# ProPrj_STC-FOC__2026-02-01.net
KiCad netlist of a schematic drawn in EasyEDA Pro
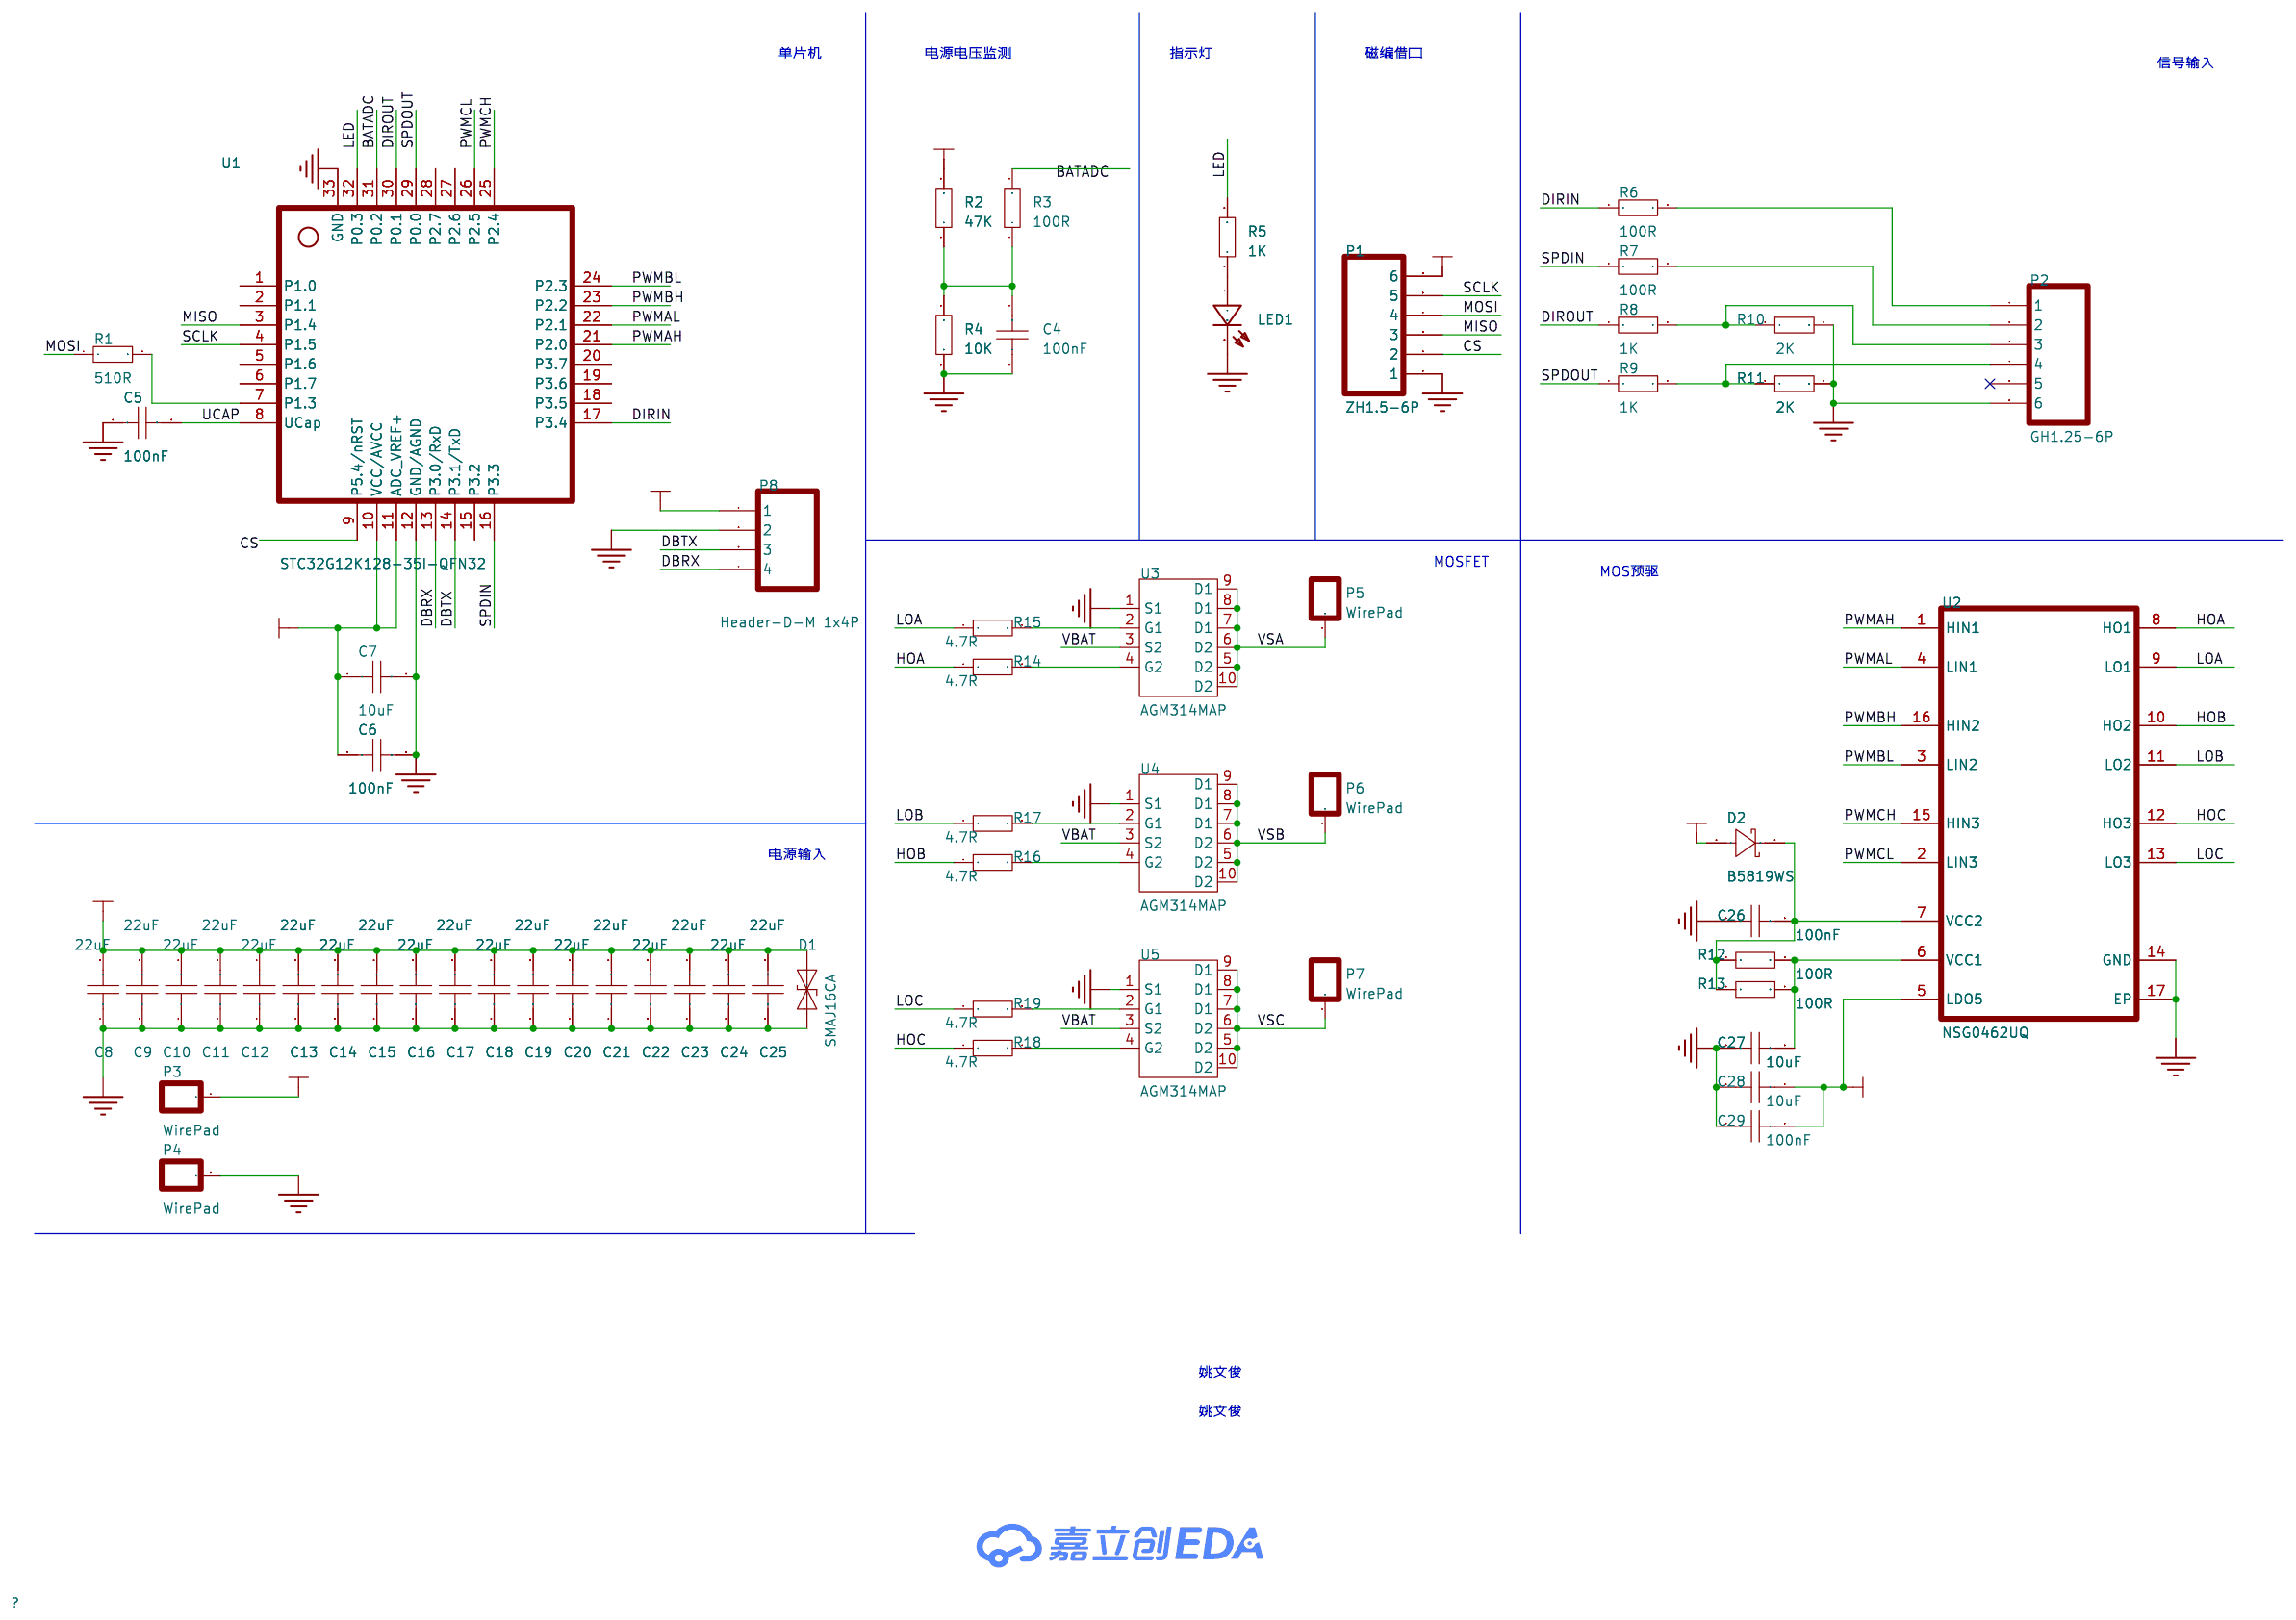
[diagram p0: schematic sheet]

(export (version "E")
  (design (tool "Eeschema 10.0.6"))
  (components
    (comp (ref "C4")
      (value "100nF")
      (footprint "easyedapro:C0603")
      (libsource (lib "easyedapro") (part "Capacitance"))
    )
    (comp (ref "C5")
      (value "100nF")
      (footprint "easyedapro:C0603")
      (libsource (lib "easyedapro") (part "Capacitance"))
    )
    (comp (ref "C6")
      (value "100nF")
      (footprint "easyedapro:C0603")
      (libsource (lib "easyedapro") (part "Capacitance"))
    )
    (comp (ref "C7")
      (value "10uF")
      (footprint "easyedapro:C0603")
      (libsource (lib "easyedapro") (part "Capacitance"))
    )
    (comp (ref "C8")
      (value "22uF")
      (footprint "easyedapro:C0603")
      (libsource (lib "easyedapro") (part "Capacitance"))
    )
    (comp (ref "C9")
      (value "22uF")
      (footprint "easyedapro:C0603")
      (libsource (lib "easyedapro") (part "Capacitance"))
    )
    (comp (ref "C10")
      (value "22uF")
      (footprint "easyedapro:C0603")
      (libsource (lib "easyedapro") (part "Capacitance"))
    )
    (comp (ref "C11")
      (value "22uF")
      (footprint "easyedapro:C0603")
      (libsource (lib "easyedapro") (part "Capacitance"))
    )
    (comp (ref "C12")
      (value "22uF")
      (footprint "easyedapro:C0603")
      (libsource (lib "easyedapro") (part "Capacitance"))
    )
    (comp (ref "C13")
      (value "22uF")
      (footprint "easyedapro:C0603")
      (libsource (lib "easyedapro") (part "Capacitance"))
    )
    (comp (ref "C14")
      (value "22uF")
      (footprint "easyedapro:C0603")
      (libsource (lib "easyedapro") (part "Capacitance"))
    )
    (comp (ref "C15")
      (value "22uF")
      (footprint "easyedapro:C0603")
      (libsource (lib "easyedapro") (part "Capacitance"))
    )
    (comp (ref "C16")
      (value "22uF")
      (footprint "easyedapro:C0603")
      (libsource (lib "easyedapro") (part "Capacitance"))
    )
    (comp (ref "C17")
      (value "22uF")
      (footprint "easyedapro:C0603")
      (libsource (lib "easyedapro") (part "Capacitance"))
    )
    (comp (ref "C18")
      (value "22uF")
      (footprint "easyedapro:C0603")
      (libsource (lib "easyedapro") (part "Capacitance"))
    )
    (comp (ref "C19")
      (value "22uF")
      (footprint "easyedapro:C0603")
      (libsource (lib "easyedapro") (part "Capacitance"))
    )
    (comp (ref "C20")
      (value "22uF")
      (footprint "easyedapro:C0603")
      (libsource (lib "easyedapro") (part "Capacitance"))
    )
    (comp (ref "C21")
      (value "22uF")
      (footprint "easyedapro:C0603")
      (libsource (lib "easyedapro") (part "Capacitance"))
    )
    (comp (ref "C22")
      (value "22uF")
      (footprint "easyedapro:C0603")
      (libsource (lib "easyedapro") (part "Capacitance"))
    )
    (comp (ref "C23")
      (value "22uF")
      (footprint "easyedapro:C0603")
      (libsource (lib "easyedapro") (part "Capacitance"))
    )
    (comp (ref "C24")
      (value "22uF")
      (footprint "easyedapro:C0603")
      (libsource (lib "easyedapro") (part "Capacitance"))
    )
    (comp (ref "C25")
      (value "22uF")
      (footprint "easyedapro:C0603")
      (libsource (lib "easyedapro") (part "Capacitance"))
    )
    (comp (ref "C26")
      (value "100nF")
      (footprint "easyedapro:C0603")
      (libsource (lib "easyedapro") (part "Capacitance"))
    )
    (comp (ref "C27")
      (value "10uF")
      (footprint "easyedapro:C0603")
      (libsource (lib "easyedapro") (part "Capacitance"))
    )
    (comp (ref "C28")
      (value "10uF")
      (footprint "easyedapro:C0603")
      (libsource (lib "easyedapro") (part "Capacitance"))
    )
    (comp (ref "C29")
      (value "100nF")
      (footprint "easyedapro:C0603")
      (libsource (lib "easyedapro") (part "Capacitance"))
    )
    (comp (ref "D1")
      (value "SMAJ16CA")
      (footprint "easyedapro:SMA_L4.4-W2.6-LS5.0-BI")
      (description "极性:双向;反向截止电压(Vrwm):16V;钳位电压:26V;峰值脉冲电流(Ipp):15.38A;峰值脉冲功率(Ppp):400W@10/1000us;击穿电压:17.8V;")
      (fields (field (name "Manufacturer") "DOWO(东沃)"))
      (libsource (lib "easyedapro") (part "SMAJ16CA_C356365"))
    )
    (comp (ref "D2")
      (value "B5819WS")
      (footprint "easyedapro:SOD-323_L1.7-W1.3-LS2.7-RD")
      (description "二极管配置:1个独立式;正向压降(Vf):900mV@3A;直流反向耐压(Vr):40V;整流电流:1A;")
      (fields (field (name "Manufacturer") "CCX(晁禾)"))
      (libsource (lib "easyedapro") (part "B5819WS_C51953485"))
    )
    (comp (ref "LED1")
      (value "LED Chip Blue")
      (footprint "easyedapro:LEDC1608(0603)-L")
      (description "蓝色贴片LED")
      (libsource (lib "easyedapro") (part "LED Chip Blue"))
    )
    (comp (ref "P1")
      (value "ZH1.5-6P")
      (footprint "easyedapro:ZH1.5-6P-SH")
      (libsource (lib "easyedapro") (part "ZH1.5-6P"))
    )
    (comp (ref "P2")
      (value "GH1.25-6P")
      (footprint "easyedapro:GH1.25-6P-SH")
      (libsource (lib "easyedapro") (part "GH1.25-6P"))
    )
    (comp (ref "P3")
      (value "WirePad")
      (footprint "easyedapro:WirePad-3x4")
      (description "线缆焊盘")
      (libsource (lib "easyedapro") (part "WirePad"))
    )
    (comp (ref "P4")
      (value "WirePad")
      (footprint "easyedapro:WirePad-3x4")
      (description "线缆焊盘")
      (libsource (lib "easyedapro") (part "WirePad"))
    )
    (comp (ref "P5")
      (value "WirePad")
      (footprint "easyedapro:WirePad-3x4")
      (description "线缆焊盘")
      (libsource (lib "easyedapro") (part "WirePad"))
    )
    (comp (ref "P6")
      (value "WirePad")
      (footprint "easyedapro:WirePad-3x4")
      (description "线缆焊盘")
      (libsource (lib "easyedapro") (part "WirePad"))
    )
    (comp (ref "P7")
      (value "WirePad")
      (footprint "easyedapro:WirePad-3x4")
      (description "线缆焊盘")
      (libsource (lib "easyedapro") (part "WirePad"))
    )
    (comp (ref "P8")
      (value "Header-D-M 1x4P")
      (footprint "easyedapro:HDR1X4-M")
      (description "1x4pin, 直插, 排针")
      (libsource (lib "easyedapro") (part "Header-D-M 1x4P"))
    )
    (comp (ref "R1") (value "510R") (footprint "easyedapro:R0402") (libsource (lib "easyedapro") (part "电阻")))
    (comp (ref "R2") (value "47K") (footprint "easyedapro:R0402") (libsource (lib "easyedapro") (part "电阻")))
    (comp (ref "R3") (value "100R") (footprint "easyedapro:R0402") (libsource (lib "easyedapro") (part "电阻")))
    (comp (ref "R4") (value "10K") (footprint "easyedapro:R0402") (libsource (lib "easyedapro") (part "电阻")))
    (comp (ref "R5") (value "1K") (footprint "easyedapro:R0402") (libsource (lib "easyedapro") (part "电阻")))
    (comp (ref "R6") (value "100R") (footprint "easyedapro:R0402") (libsource (lib "easyedapro") (part "电阻")))
    (comp (ref "R7") (value "100R") (footprint "easyedapro:R0402") (libsource (lib "easyedapro") (part "电阻")))
    (comp (ref "R8") (value "1K") (footprint "easyedapro:R0402") (libsource (lib "easyedapro") (part "电阻")))
    (comp (ref "R9") (value "1K") (footprint "easyedapro:R0402") (libsource (lib "easyedapro") (part "电阻")))
    (comp (ref "R10") (value "2K") (footprint "easyedapro:R0402") (libsource (lib "easyedapro") (part "电阻")))
    (comp (ref "R11") (value "2K") (footprint "easyedapro:R0402") (libsource (lib "easyedapro") (part "电阻")))
    (comp (ref "R12")
      (value "100R")
      (footprint "easyedapro:R0402")
      (libsource (lib "easyedapro") (part "电阻"))
    )
    (comp (ref "R13")
      (value "100R")
      (footprint "easyedapro:R0402")
      (libsource (lib "easyedapro") (part "电阻"))
    )
    (comp (ref "R14")
      (value "4.7R")
      (footprint "easyedapro:R0402")
      (libsource (lib "easyedapro") (part "电阻"))
    )
    (comp (ref "R15")
      (value "4.7R")
      (footprint "easyedapro:R0402")
      (libsource (lib "easyedapro") (part "电阻"))
    )
    (comp (ref "R16")
      (value "4.7R")
      (footprint "easyedapro:R0402")
      (libsource (lib "easyedapro") (part "电阻"))
    )
    (comp (ref "R17")
      (value "4.7R")
      (footprint "easyedapro:R0402")
      (libsource (lib "easyedapro") (part "电阻"))
    )
    (comp (ref "R18")
      (value "4.7R")
      (footprint "easyedapro:R0402")
      (libsource (lib "easyedapro") (part "电阻"))
    )
    (comp (ref "R19")
      (value "4.7R")
      (footprint "easyedapro:R0402")
      (libsource (lib "easyedapro") (part "电阻"))
    )
    (comp (ref "U1")
      (value "STC32G12K128-35I-QFN32")
      (footprint "easyedapro:QFN32-4x4")
      (libsource (lib "easyedapro") (part "STC32G12K128-35I-QFN32"))
    )
    (comp (ref "U2")
      (value "NSG0462UQ")
      (footprint "easyedapro:QFN16-3x3-0.5")
      (description "NSG0462UQ 三相栅极驱动器")
      (libsource (lib "easyedapro") (part "NSG0462UQ"))
    )
    (comp (ref "U3")
      (value "AGM314MAP")
      (footprint "easyedapro:PDFN-8_L3.2-W3.1-P0.65-LS3.4-BL-EP2")
      (fields (field (name "Manufacturer") "AGMSEMI(芯控源)"))
      (libsource (lib "easyedapro") (part "AGM314MAP"))
    )
    (comp (ref "U4")
      (value "AGM314MAP")
      (footprint "easyedapro:PDFN-8_L3.2-W3.1-P0.65-LS3.4-BL-EP2")
      (fields (field (name "Manufacturer") "AGMSEMI(芯控源)"))
      (libsource (lib "easyedapro") (part "AGM314MAP"))
    )
    (comp (ref "U5")
      (value "AGM314MAP")
      (footprint "easyedapro:PDFN-8_L3.2-W3.1-P0.65-LS3.4-BL-EP2")
      (fields (field (name "Manufacturer") "AGMSEMI(芯控源)"))
      (libsource (lib "easyedapro") (part "AGM314MAP"))
    )
  )
  (nets
    (net (code "1") (name "/BATADC") (class "Default")
      (node (ref "R3") (pin "2") (pinfunction "2_2") (pintype "input"))
      (node (ref "U1") (pin "31") (pinfunction "P0.2_31") (pintype "unspecified"))
    )
    (net (code "2") (name "/CS") (class "Default")
      (node (ref "P1") (pin "2") (pinfunction "2_2") (pintype "unspecified"))
      (node (ref "U1") (pin "9") (pinfunction "P5.4/nRST_9") (pintype "unspecified"))
    )
    (net (code "3") (name "/DBRX") (class "Default")
      (node (ref "P8") (pin "4") (pinfunction "4_4") (pintype "unspecified"))
      (node (ref "U1") (pin "13") (pinfunction "P3.0/RxD_13") (pintype "unspecified"))
    )
    (net (code "4") (name "/DBTX") (class "Default")
      (node (ref "P8") (pin "3") (pinfunction "3_3") (pintype "unspecified"))
      (node (ref "U1") (pin "14") (pinfunction "P3.1/TxD_14") (pintype "unspecified"))
    )
    (net (code "5") (name "/DIRIN") (class "Default")
      (node (ref "R6") (pin "1") (pinfunction "1_1") (pintype "input"))
      (node (ref "U1") (pin "17") (pinfunction "P3.4_17") (pintype "unspecified"))
    )
    (net (code "6") (name "/DIROUT") (class "Default")
      (node (ref "R8") (pin "1") (pinfunction "1_1") (pintype "input"))
      (node (ref "U1") (pin "30") (pinfunction "P0.1_30") (pintype "unspecified"))
    )
    (net (code "7") (name "/HOA") (class "Default")
      (node (ref "R14") (pin "1") (pinfunction "1_1") (pintype "input"))
      (node (ref "U2") (pin "8") (pinfunction "HO1_8") (pintype "unspecified"))
    )
    (net (code "8") (name "/HOB") (class "Default")
      (node (ref "R16") (pin "1") (pinfunction "1_1") (pintype "input"))
      (node (ref "U2") (pin "10") (pinfunction "HO2_10") (pintype "unspecified"))
    )
    (net (code "9") (name "/HOC") (class "Default")
      (node (ref "R18") (pin "1") (pinfunction "1_1") (pintype "input"))
      (node (ref "U2") (pin "12") (pinfunction "HO3_12") (pintype "unspecified"))
    )
    (net (code "10") (name "/LED") (class "Default")
      (node (ref "R5") (pin "2") (pinfunction "2_2") (pintype "input"))
      (node (ref "U1") (pin "32") (pinfunction "P0.3_32") (pintype "unspecified"))
    )
    (net (code "11") (name "/LOA") (class "Default")
      (node (ref "R15") (pin "1") (pinfunction "1_1") (pintype "input"))
      (node (ref "U2") (pin "9") (pinfunction "LO1_9") (pintype "unspecified"))
    )
    (net (code "12") (name "/LOB") (class "Default")
      (node (ref "R17") (pin "1") (pinfunction "1_1") (pintype "input"))
      (node (ref "U2") (pin "11") (pinfunction "LO2_11") (pintype "unspecified"))
    )
    (net (code "13") (name "/LOC") (class "Default")
      (node (ref "R19") (pin "1") (pinfunction "1_1") (pintype "input"))
      (node (ref "U2") (pin "13") (pinfunction "LO3_13") (pintype "unspecified"))
    )
    (net (code "14") (name "/MISO") (class "Default")
      (node (ref "P1") (pin "3") (pinfunction "3_3") (pintype "unspecified"))
      (node (ref "U1") (pin "3") (pinfunction "P1.4_3") (pintype "unspecified"))
    )
    (net (code "15") (name "/MOSI") (class "Default")
      (node (ref "P1") (pin "4") (pinfunction "4_4") (pintype "unspecified"))
      (node (ref "R1") (pin "1") (pinfunction "1_1") (pintype "input"))
    )
    (net (code "16") (name "/PWMAH") (class "Default")
      (node (ref "U1") (pin "21") (pinfunction "P2.0_21") (pintype "unspecified"))
      (node (ref "U2") (pin "1") (pinfunction "HIN1_1") (pintype "unspecified"))
    )
    (net (code "17") (name "/PWMAL") (class "Default")
      (node (ref "U1") (pin "22") (pinfunction "P2.1_22") (pintype "unspecified"))
      (node (ref "U2") (pin "4") (pinfunction "LIN1_4") (pintype "unspecified"))
    )
    (net (code "18") (name "/PWMBH") (class "Default")
      (node (ref "U1") (pin "23") (pinfunction "P2.2_23") (pintype "unspecified"))
      (node (ref "U2") (pin "16") (pinfunction "HIN2_16") (pintype "unspecified"))
    )
    (net (code "19") (name "/PWMBL") (class "Default")
      (node (ref "U1") (pin "24") (pinfunction "P2.3_24") (pintype "unspecified"))
      (node (ref "U2") (pin "3") (pinfunction "LIN2_3") (pintype "unspecified"))
    )
    (net (code "20") (name "/PWMCH") (class "Default")
      (node (ref "U1") (pin "25") (pinfunction "P2.4_25") (pintype "unspecified"))
      (node (ref "U2") (pin "15") (pinfunction "HIN3_15") (pintype "unspecified"))
    )
    (net (code "21") (name "/PWMCL") (class "Default")
      (node (ref "U1") (pin "26") (pinfunction "P2.5_26") (pintype "unspecified"))
      (node (ref "U2") (pin "2") (pinfunction "LIN3_2") (pintype "unspecified"))
    )
    (net (code "22") (name "/SCLK") (class "Default")
      (node (ref "P1") (pin "5") (pinfunction "5_5") (pintype "unspecified"))
      (node (ref "U1") (pin "4") (pinfunction "P1.5_4") (pintype "unspecified"))
    )
    (net (code "23") (name "/SPDIN") (class "Default")
      (node (ref "R7") (pin "1") (pinfunction "1_1") (pintype "input"))
      (node (ref "U1") (pin "16") (pinfunction "P3.3_16") (pintype "unspecified"))
    )
    (net (code "24") (name "/SPDOUT") (class "Default")
      (node (ref "R9") (pin "1") (pinfunction "1_1") (pintype "input"))
      (node (ref "U1") (pin "29") (pinfunction "P0.0_29") (pintype "unspecified"))
    )
    (net (code "25") (name "/UCAP") (class "Default")
      (node (ref "C5") (pin "2") (pinfunction "2_2") (pintype "input"))
      (node (ref "U1") (pin "8") (pinfunction "UCap_8") (pintype "unspecified"))
    )
    (net (code "26") (name "/VSA") (class "Default")
      (node (ref "P5") (pin "1") (pinfunction "1_1") (pintype "unspecified"))
      (node (ref "U3") (pin "10") (pinfunction "D2_10") (pintype "unspecified"))
      (node (ref "U3") (pin "5") (pinfunction "D2_5") (pintype "unspecified"))
      (node (ref "U3") (pin "6") (pinfunction "D2_6") (pintype "unspecified"))
      (node (ref "U3") (pin "7") (pinfunction "D1_7") (pintype "unspecified"))
      (node (ref "U3") (pin "8") (pinfunction "D1_8") (pintype "unspecified"))
      (node (ref "U3") (pin "9") (pinfunction "D1_9") (pintype "unspecified"))
    )
    (net (code "27") (name "/VSB") (class "Default")
      (node (ref "P6") (pin "1") (pinfunction "1_1") (pintype "unspecified"))
      (node (ref "U4") (pin "10") (pinfunction "D2_10") (pintype "unspecified"))
      (node (ref "U4") (pin "5") (pinfunction "D2_5") (pintype "unspecified"))
      (node (ref "U4") (pin "6") (pinfunction "D2_6") (pintype "unspecified"))
      (node (ref "U4") (pin "7") (pinfunction "D1_7") (pintype "unspecified"))
      (node (ref "U4") (pin "8") (pinfunction "D1_8") (pintype "unspecified"))
      (node (ref "U4") (pin "9") (pinfunction "D1_9") (pintype "unspecified"))
    )
    (net (code "28") (name "/VSC") (class "Default")
      (node (ref "P7") (pin "1") (pinfunction "1_1") (pintype "unspecified"))
      (node (ref "U5") (pin "10") (pinfunction "D2_10") (pintype "unspecified"))
      (node (ref "U5") (pin "5") (pinfunction "D2_5") (pintype "unspecified"))
      (node (ref "U5") (pin "6") (pinfunction "D2_6") (pintype "unspecified"))
      (node (ref "U5") (pin "7") (pinfunction "D1_7") (pintype "unspecified"))
      (node (ref "U5") (pin "8") (pinfunction "D1_8") (pintype "unspecified"))
      (node (ref "U5") (pin "9") (pinfunction "D1_9") (pintype "unspecified"))
    )
    (net (code "29") (name "GND") (class "Default")
      (node (ref "C10") (pin "1") (pinfunction "1_1") (pintype "input"))
      (node (ref "C11") (pin "1") (pinfunction "1_1") (pintype "input"))
      (node (ref "C12") (pin "1") (pinfunction "1_1") (pintype "input"))
      (node (ref "C13") (pin "1") (pinfunction "1_1") (pintype "input"))
      (node (ref "C14") (pin "1") (pinfunction "1_1") (pintype "input"))
      (node (ref "C15") (pin "1") (pinfunction "1_1") (pintype "input"))
      (node (ref "C16") (pin "1") (pinfunction "1_1") (pintype "input"))
      (node (ref "C17") (pin "1") (pinfunction "1_1") (pintype "input"))
      (node (ref "C18") (pin "1") (pinfunction "1_1") (pintype "input"))
      (node (ref "C19") (pin "1") (pinfunction "1_1") (pintype "input"))
      (node (ref "C20") (pin "1") (pinfunction "1_1") (pintype "input"))
      (node (ref "C21") (pin "1") (pinfunction "1_1") (pintype "input"))
      (node (ref "C22") (pin "1") (pinfunction "1_1") (pintype "input"))
      (node (ref "C23") (pin "1") (pinfunction "1_1") (pintype "input"))
      (node (ref "C24") (pin "1") (pinfunction "1_1") (pintype "input"))
      (node (ref "C25") (pin "1") (pinfunction "1_1") (pintype "input"))
      (node (ref "C26") (pin "1") (pinfunction "1_1") (pintype "input"))
      (node (ref "C27") (pin "1") (pinfunction "1_1") (pintype "input"))
      (node (ref "C28") (pin "1") (pinfunction "1_1") (pintype "input"))
      (node (ref "C29") (pin "1") (pinfunction "1_1") (pintype "input"))
      (node (ref "C4") (pin "1") (pinfunction "1_1") (pintype "input"))
      (node (ref "C5") (pin "1") (pinfunction "1_1") (pintype "input"))
      (node (ref "C6") (pin "2") (pinfunction "2_2") (pintype "input"))
      (node (ref "C7") (pin "2") (pinfunction "2_2") (pintype "input"))
      (node (ref "C8") (pin "1") (pinfunction "1_1") (pintype "input"))
      (node (ref "C9") (pin "1") (pinfunction "1_1") (pintype "input"))
      (node (ref "D1") (pin "2") (pinfunction "A_2") (pintype "unspecified"))
      (node (ref "LED1") (pin "C") (pinfunction "C_C") (pintype "unspecified"))
      (node (ref "P1") (pin "1") (pinfunction "1_1") (pintype "unspecified"))
      (node (ref "P2") (pin "6") (pinfunction "6_6") (pintype "unspecified"))
      (node (ref "P4") (pin "1") (pinfunction "1_1") (pintype "unspecified"))
      (node (ref "P8") (pin "2") (pinfunction "2_2") (pintype "unspecified"))
      (node (ref "R10") (pin "2") (pinfunction "2_2") (pintype "input"))
      (node (ref "R11") (pin "2") (pinfunction "2_2") (pintype "input"))
      (node (ref "R4") (pin "1") (pinfunction "1_1") (pintype "input"))
      (node (ref "U1") (pin "12") (pinfunction "GND/AGND_12") (pintype "unspecified"))
      (node (ref "U1") (pin "33") (pinfunction "GND_33") (pintype "unspecified"))
      (node (ref "U2") (pin "14") (pinfunction "GND_14") (pintype "unspecified"))
      (node (ref "U2") (pin "17") (pinfunction "EP_17") (pintype "unspecified"))
      (node (ref "U3") (pin "1") (pinfunction "S1_1") (pintype "unspecified"))
      (node (ref "U4") (pin "1") (pinfunction "S1_1") (pintype "unspecified"))
      (node (ref "U5") (pin "1") (pinfunction "S1_1") (pintype "unspecified"))
    )
    (net (code "30") (name "Net-(C4-Pad2)") (class "Default")
      (node (ref "C4") (pin "2") (pinfunction "2_2") (pintype "input"))
      (node (ref "R2") (pin "1") (pinfunction "1_1") (pintype "input"))
      (node (ref "R3") (pin "1") (pinfunction "1_1") (pintype "input"))
      (node (ref "R4") (pin "2") (pinfunction "2_2") (pintype "input"))
    )
    (net (code "31") (name "Net-(D2-K)") (class "Default")
      (node (ref "C26") (pin "2") (pinfunction "2_2") (pintype "input"))
      (node (ref "D2") (pin "1") (pinfunction "K_1") (pintype "unspecified"))
      (node (ref "R12") (pin "1") (pinfunction "1_1") (pintype "input"))
      (node (ref "R13") (pin "1") (pinfunction "1_1") (pintype "input"))
      (node (ref "U2") (pin "7") (pinfunction "VCC2_7") (pintype "unspecified"))
    )
    (net (code "32") (name "Net-(LED1-PadA)") (class "Default")
      (node (ref "LED1") (pin "A") (pinfunction "A_A") (pintype "unspecified"))
      (node (ref "R5") (pin "1") (pinfunction "1_1") (pintype "input"))
    )
    (net (code "33") (name "Net-(P2-Pad1)") (class "Default")
      (node (ref "P2") (pin "1") (pinfunction "1_1") (pintype "unspecified"))
      (node (ref "R6") (pin "2") (pinfunction "2_2") (pintype "input"))
    )
    (net (code "34") (name "Net-(P2-Pad2)") (class "Default")
      (node (ref "P2") (pin "2") (pinfunction "2_2") (pintype "unspecified"))
      (node (ref "R7") (pin "2") (pinfunction "2_2") (pintype "input"))
    )
    (net (code "35") (name "Net-(P2-Pad3)") (class "Default")
      (node (ref "P2") (pin "3") (pinfunction "3_3") (pintype "unspecified"))
      (node (ref "R10") (pin "1") (pinfunction "1_1") (pintype "input"))
      (node (ref "R8") (pin "2") (pinfunction "2_2") (pintype "input"))
    )
    (net (code "36") (name "Net-(P2-Pad4)") (class "Default")
      (node (ref "P2") (pin "4") (pinfunction "4_4") (pintype "unspecified"))
      (node (ref "R11") (pin "1") (pinfunction "1_1") (pintype "input"))
      (node (ref "R9") (pin "2") (pinfunction "2_2") (pintype "input"))
    )
    (net (code "37") (name "Net-(U1-P1.3)") (class "Default")
      (node (ref "R1") (pin "2") (pinfunction "2_2") (pintype "input"))
      (node (ref "U1") (pin "7") (pinfunction "P1.3_7") (pintype "unspecified"))
    )
    (net (code "38") (name "Net-(U2-VCC1)") (class "Default")
      (node (ref "C27") (pin "2") (pinfunction "2_2") (pintype "input"))
      (node (ref "R12") (pin "2") (pinfunction "2_2") (pintype "input"))
      (node (ref "R13") (pin "2") (pinfunction "2_2") (pintype "input"))
      (node (ref "U2") (pin "6") (pinfunction "VCC1_6") (pintype "unspecified"))
    )
    (net (code "39") (name "Net-(U3-G1)") (class "Default")
      (node (ref "R15") (pin "2") (pinfunction "2_2") (pintype "input"))
      (node (ref "U3") (pin "2") (pinfunction "G1_2") (pintype "unspecified"))
    )
    (net (code "40") (name "Net-(U3-G2)") (class "Default")
      (node (ref "R14") (pin "2") (pinfunction "2_2") (pintype "input"))
      (node (ref "U3") (pin "4") (pinfunction "G2_4") (pintype "unspecified"))
    )
    (net (code "41") (name "Net-(U4-G1)") (class "Default")
      (node (ref "R17") (pin "2") (pinfunction "2_2") (pintype "input"))
      (node (ref "U4") (pin "2") (pinfunction "G1_2") (pintype "unspecified"))
    )
    (net (code "42") (name "Net-(U4-G2)") (class "Default")
      (node (ref "R16") (pin "2") (pinfunction "2_2") (pintype "input"))
      (node (ref "U4") (pin "4") (pinfunction "G2_4") (pintype "unspecified"))
    )
    (net (code "43") (name "Net-(U5-G1)") (class "Default")
      (node (ref "R19") (pin "2") (pinfunction "2_2") (pintype "input"))
      (node (ref "U5") (pin "2") (pinfunction "G1_2") (pintype "unspecified"))
    )
    (net (code "44") (name "Net-(U5-G2)") (class "Default")
      (node (ref "R18") (pin "2") (pinfunction "2_2") (pintype "input"))
      (node (ref "U5") (pin "4") (pinfunction "G2_4") (pintype "unspecified"))
    )
    (net (code "45") (name "VBAT") (class "Default")
      (node (ref "C10") (pin "2") (pinfunction "2_2") (pintype "input"))
      (node (ref "C11") (pin "2") (pinfunction "2_2") (pintype "input"))
      (node (ref "C12") (pin "2") (pinfunction "2_2") (pintype "input"))
      (node (ref "C13") (pin "2") (pinfunction "2_2") (pintype "input"))
      (node (ref "C14") (pin "2") (pinfunction "2_2") (pintype "input"))
      (node (ref "C15") (pin "2") (pinfunction "2_2") (pintype "input"))
      (node (ref "C16") (pin "2") (pinfunction "2_2") (pintype "input"))
      (node (ref "C17") (pin "2") (pinfunction "2_2") (pintype "input"))
      (node (ref "C18") (pin "2") (pinfunction "2_2") (pintype "input"))
      (node (ref "C19") (pin "2") (pinfunction "2_2") (pintype "input"))
      (node (ref "C20") (pin "2") (pinfunction "2_2") (pintype "input"))
      (node (ref "C21") (pin "2") (pinfunction "2_2") (pintype "input"))
      (node (ref "C22") (pin "2") (pinfunction "2_2") (pintype "input"))
      (node (ref "C23") (pin "2") (pinfunction "2_2") (pintype "input"))
      (node (ref "C24") (pin "2") (pinfunction "2_2") (pintype "input"))
      (node (ref "C25") (pin "2") (pinfunction "2_2") (pintype "input"))
      (node (ref "C8") (pin "2") (pinfunction "2_2") (pintype "input"))
      (node (ref "C9") (pin "2") (pinfunction "2_2") (pintype "input"))
      (node (ref "D1") (pin "1") (pinfunction "K_1") (pintype "unspecified"))
      (node (ref "D2") (pin "2") (pinfunction "A_2") (pintype "unspecified"))
      (node (ref "P3") (pin "1") (pinfunction "1_1") (pintype "unspecified"))
      (node (ref "R2") (pin "2") (pinfunction "2_2") (pintype "input"))
      (node (ref "U3") (pin "3") (pinfunction "S2_3") (pintype "unspecified"))
      (node (ref "U4") (pin "3") (pinfunction "S2_3") (pintype "unspecified"))
      (node (ref "U5") (pin "3") (pinfunction "S2_3") (pintype "unspecified"))
    )
    (net (code "46") (name "VCCMCU") (class "Default")
      (node (ref "C28") (pin "2") (pinfunction "2_2") (pintype "input"))
      (node (ref "C29") (pin "2") (pinfunction "2_2") (pintype "input"))
      (node (ref "C6") (pin "1") (pinfunction "1_1") (pintype "input"))
      (node (ref "C7") (pin "1") (pinfunction "1_1") (pintype "input"))
      (node (ref "P1") (pin "6") (pinfunction "6_6") (pintype "unspecified"))
      (node (ref "P8") (pin "1") (pinfunction "1_1") (pintype "unspecified"))
      (node (ref "U1") (pin "10") (pinfunction "VCC/AVCC_10") (pintype "unspecified"))
      (node (ref "U1") (pin "11") (pinfunction "ADC_VREF+_11") (pintype "unspecified"))
      (node (ref "U2") (pin "5") (pinfunction "LDO5_5") (pintype "unspecified"))
    )
    (net (code "47") (name "unconnected-(P2-Pad5)") (class "Default")
      (node (ref "P2") (pin "5") (pinfunction "5_5") (pintype "unspecified+no_connect"))
    )
    (net (code "48") (name "unconnected-(U1-P1.0-Pad1)") (class "Default")
      (node (ref "U1") (pin "1") (pinfunction "P1.0_1") (pintype "unspecified"))
    )
    (net (code "49") (name "unconnected-(U1-P1.1-Pad2)") (class "Default")
      (node (ref "U1") (pin "2") (pinfunction "P1.1_2") (pintype "unspecified"))
    )
    (net (code "50") (name "unconnected-(U1-P1.6-Pad5)") (class "Default")
      (node (ref "U1") (pin "5") (pinfunction "P1.6_5") (pintype "unspecified"))
    )
    (net (code "51") (name "unconnected-(U1-P1.7-Pad6)") (class "Default")
      (node (ref "U1") (pin "6") (pinfunction "P1.7_6") (pintype "unspecified"))
    )
    (net (code "52") (name "unconnected-(U1-P2.6-Pad27)") (class "Default")
      (node (ref "U1") (pin "27") (pinfunction "P2.6_27") (pintype "unspecified"))
    )
    (net (code "53") (name "unconnected-(U1-P2.7-Pad28)") (class "Default")
      (node (ref "U1") (pin "28") (pinfunction "P2.7_28") (pintype "unspecified"))
    )
    (net (code "54") (name "unconnected-(U1-P3.2-Pad15)") (class "Default")
      (node (ref "U1") (pin "15") (pinfunction "P3.2_15") (pintype "unspecified"))
    )
    (net (code "55") (name "unconnected-(U1-P3.5-Pad18)") (class "Default")
      (node (ref "U1") (pin "18") (pinfunction "P3.5_18") (pintype "unspecified"))
    )
    (net (code "56") (name "unconnected-(U1-P3.6-Pad19)") (class "Default")
      (node (ref "U1") (pin "19") (pinfunction "P3.6_19") (pintype "unspecified"))
    )
    (net (code "57") (name "unconnected-(U1-P3.7-Pad20)") (class "Default")
      (node (ref "U1") (pin "20") (pinfunction "P3.7_20") (pintype "unspecified"))
    )
  )
)
